# lecteur_8.net
KiCad netlist of a schematic drawn in Altium Designer
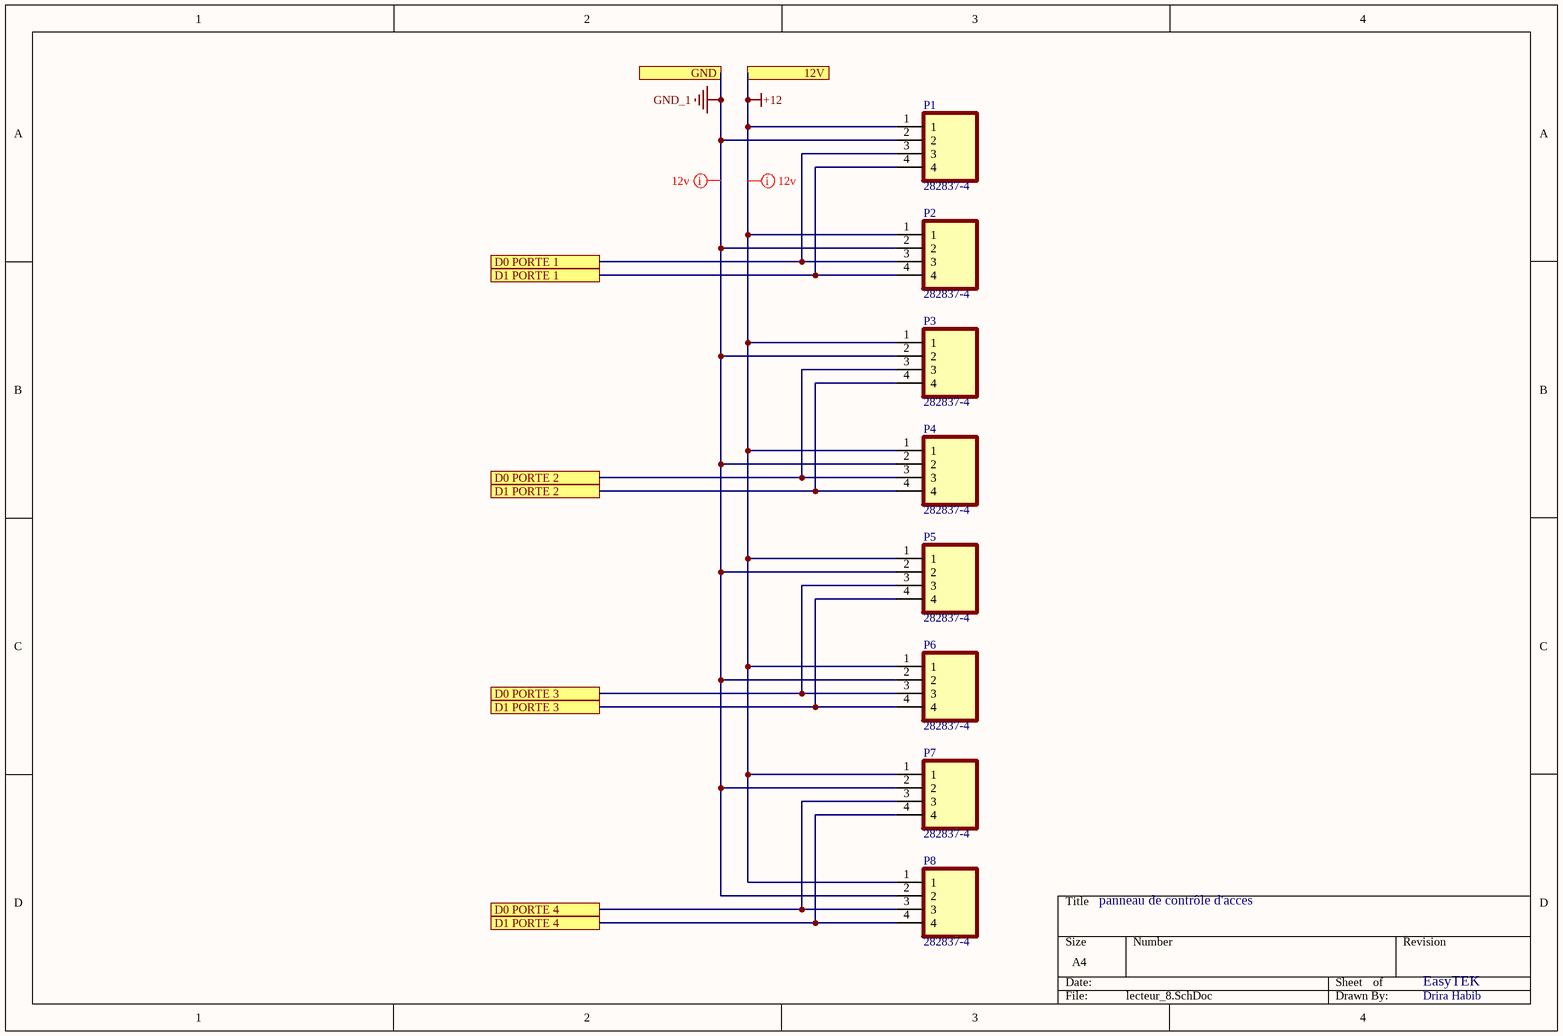
[diagram p0: lecteur_8.SchDoc]

(export (version "E")
  (design (tool "Eeschema 10.0.6"))
  (components
    (comp (ref "P1")
      (value "282837-4")
      (footprint "TE_282837-4")
      (description "4 Position Wire to Board Terminal Block Horizontal with Board 0.200 (5.08mm) Through Hole")
      (fields (field (name "MF") "TE Connectivity"))
      (libsource (lib "controlpannel") (part "282837-4"))
    )
    (comp (ref "P2")
      (value "282837-4")
      (footprint "TE_282837-4")
      (description "4 Position Wire to Board Terminal Block Horizontal with Board 0.200 (5.08mm) Through Hole")
      (fields (field (name "MF") "TE Connectivity"))
      (libsource (lib "controlpannel") (part "282837-4"))
    )
    (comp (ref "P3")
      (value "282837-4")
      (footprint "TE_282837-4")
      (description "4 Position Wire to Board Terminal Block Horizontal with Board 0.200 (5.08mm) Through Hole")
      (fields (field (name "MF") "TE Connectivity"))
      (libsource (lib "controlpannel") (part "282837-4"))
    )
    (comp (ref "P4")
      (value "282837-4")
      (footprint "TE_282837-4")
      (description "4 Position Wire to Board Terminal Block Horizontal with Board 0.200 (5.08mm) Through Hole")
      (fields (field (name "MF") "TE Connectivity"))
      (libsource (lib "controlpannel") (part "282837-4"))
    )
    (comp (ref "P5")
      (value "282837-4")
      (footprint "TE_282837-4")
      (description "4 Position Wire to Board Terminal Block Horizontal with Board 0.200 (5.08mm) Through Hole")
      (fields (field (name "MF") "TE Connectivity"))
      (libsource (lib "controlpannel") (part "282837-4"))
    )
    (comp (ref "P6")
      (value "282837-4")
      (footprint "TE_282837-4")
      (description "4 Position Wire to Board Terminal Block Horizontal with Board 0.200 (5.08mm) Through Hole")
      (fields (field (name "MF") "TE Connectivity"))
      (libsource (lib "controlpannel") (part "282837-4"))
    )
    (comp (ref "P7")
      (value "282837-4")
      (footprint "TE_282837-4")
      (description "4 Position Wire to Board Terminal Block Horizontal with Board 0.200 (5.08mm) Through Hole")
      (fields (field (name "MF") "TE Connectivity"))
      (libsource (lib "controlpannel") (part "282837-4"))
    )
    (comp (ref "P8")
      (value "282837-4")
      (footprint "TE_282837-4")
      (description "4 Position Wire to Board Terminal Block Horizontal with Board 0.200 (5.08mm) Through Hole")
      (fields (field (name "MF") "TE Connectivity"))
      (libsource (lib "controlpannel") (part "282837-4"))
    )
  )
  (nets
    (net (code "1") (name "+12") (class "Default")
      (node (ref "P1") (pin "1") (pinfunction "1_1") (pintype "passive"))
      (node (ref "P2") (pin "1") (pinfunction "1_1") (pintype "passive"))
      (node (ref "P3") (pin "1") (pinfunction "1_1") (pintype "passive"))
      (node (ref "P4") (pin "1") (pinfunction "1_1") (pintype "passive"))
      (node (ref "P5") (pin "1") (pinfunction "1_1") (pintype "passive"))
      (node (ref "P6") (pin "1") (pinfunction "1_1") (pintype "passive"))
      (node (ref "P7") (pin "1") (pinfunction "1_1") (pintype "passive"))
      (node (ref "P8") (pin "1") (pinfunction "1_1") (pintype "passive"))
    )
    (net (code "2") (name "/D0 PORTE 1") (class "Default")
      (node (ref "P1") (pin "3") (pinfunction "3_3") (pintype "passive"))
      (node (ref "P2") (pin "3") (pinfunction "3_3") (pintype "passive"))
    )
    (net (code "3") (name "/D0 PORTE 2") (class "Default")
      (node (ref "P3") (pin "3") (pinfunction "3_3") (pintype "passive"))
      (node (ref "P4") (pin "3") (pinfunction "3_3") (pintype "passive"))
    )
    (net (code "4") (name "/D0 PORTE 3") (class "Default")
      (node (ref "P5") (pin "3") (pinfunction "3_3") (pintype "passive"))
      (node (ref "P6") (pin "3") (pinfunction "3_3") (pintype "passive"))
    )
    (net (code "5") (name "/D0 PORTE 4") (class "Default")
      (node (ref "P7") (pin "3") (pinfunction "3_3") (pintype "passive"))
      (node (ref "P8") (pin "3") (pinfunction "3_3") (pintype "passive"))
    )
    (net (code "6") (name "/D1 PORTE 1") (class "Default")
      (node (ref "P1") (pin "4") (pinfunction "4_4") (pintype "passive"))
      (node (ref "P2") (pin "4") (pinfunction "4_4") (pintype "passive"))
    )
    (net (code "7") (name "/D1 PORTE 2") (class "Default")
      (node (ref "P3") (pin "4") (pinfunction "4_4") (pintype "passive"))
      (node (ref "P4") (pin "4") (pinfunction "4_4") (pintype "passive"))
    )
    (net (code "8") (name "/D1 PORTE 3") (class "Default")
      (node (ref "P5") (pin "4") (pinfunction "4_4") (pintype "passive"))
      (node (ref "P6") (pin "4") (pinfunction "4_4") (pintype "passive"))
    )
    (net (code "9") (name "/D1 PORTE 4") (class "Default")
      (node (ref "P7") (pin "4") (pinfunction "4_4") (pintype "passive"))
      (node (ref "P8") (pin "4") (pinfunction "4_4") (pintype "passive"))
    )
    (net (code "10") (name "GND_1") (class "Default")
      (node (ref "P1") (pin "2") (pinfunction "2_2") (pintype "passive"))
      (node (ref "P2") (pin "2") (pinfunction "2_2") (pintype "passive"))
      (node (ref "P3") (pin "2") (pinfunction "2_2") (pintype "passive"))
      (node (ref "P4") (pin "2") (pinfunction "2_2") (pintype "passive"))
      (node (ref "P5") (pin "2") (pinfunction "2_2") (pintype "passive"))
      (node (ref "P6") (pin "2") (pinfunction "2_2") (pintype "passive"))
      (node (ref "P7") (pin "2") (pinfunction "2_2") (pintype "passive"))
      (node (ref "P8") (pin "2") (pinfunction "2_2") (pintype "passive"))
    )
  )
)
